# hbridge_v2.net
KiCad netlist of a schematic drawn in EAGLE
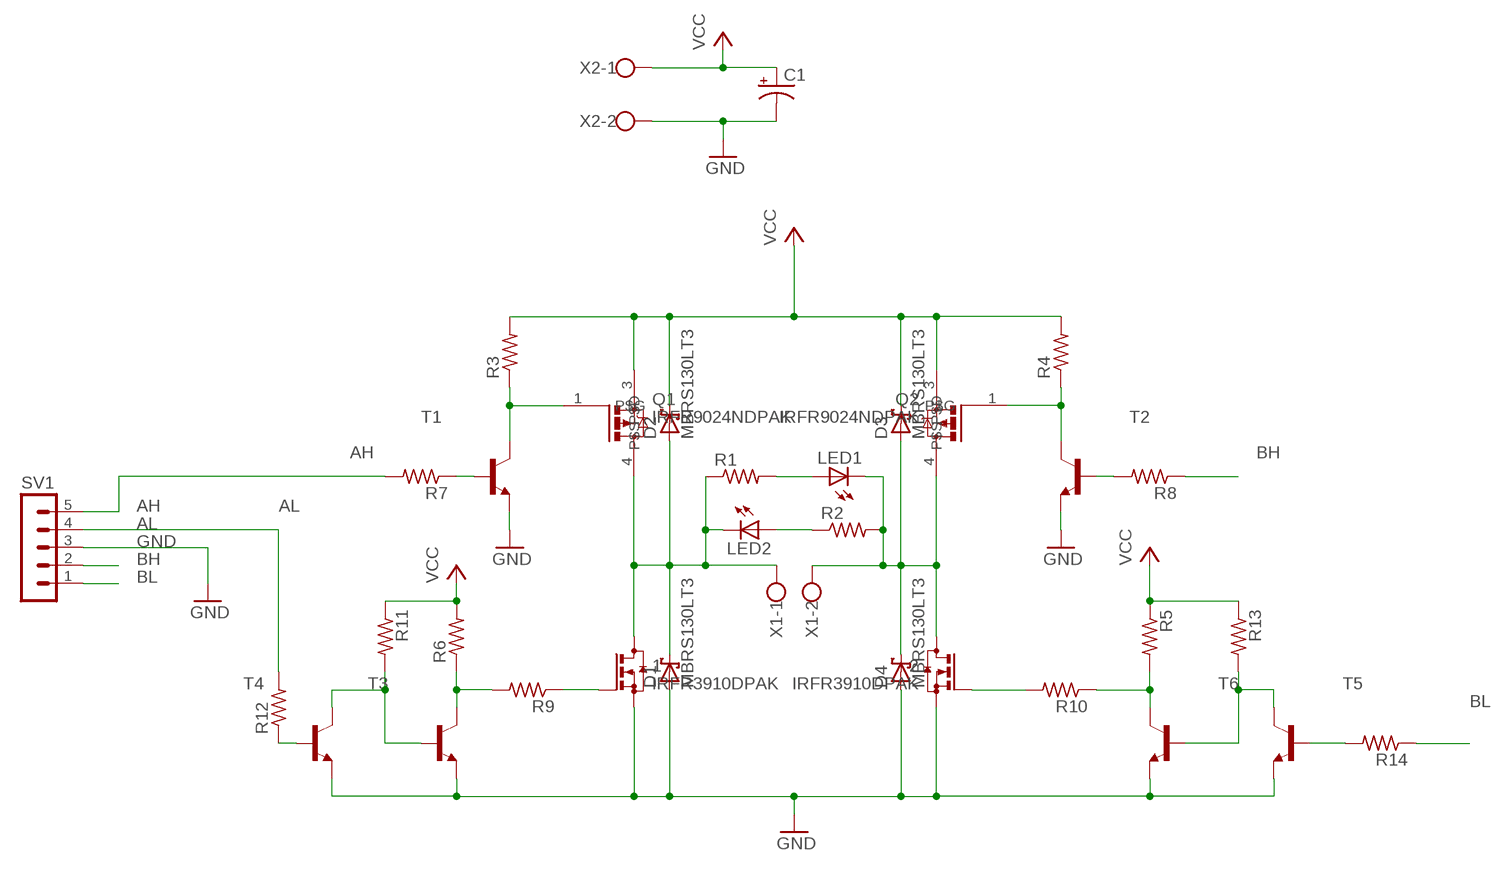
[diagram p0: schematic, sheet 1]

(export (version "E")
  (design (tool "Eeschema 10.0.6"))
  (components
    (comp (ref "1")
      (value "IRFR3910DPAK")
      (footprint "eagle-import:D-PAK_TO252AA")
      (libsource (lib "eagle-import") (part "IRFR3910DPAK"))
    )
    (comp (ref "2")
      (value "IRFR3910DPAK")
      (footprint "eagle-import:D-PAK_TO252AA")
      (libsource (lib "eagle-import") (part "IRFR3910DPAK"))
    )
    (comp (ref "C1")
      (value "CPOL-USE5-10.5")
      (footprint "eagle-import:E5-10,5")
      (libsource (lib "eagle-import") (part "CPOL-USE5-10.5"))
    )
    (comp (ref "D1")
      (value "MBRS130LT3")
      (footprint "eagle-import:SMB")
      (libsource (lib "eagle-import") (part "MBRS130LT3"))
    )
    (comp (ref "D2")
      (value "MBRS130LT3")
      (footprint "eagle-import:SMB")
      (libsource (lib "eagle-import") (part "MBRS130LT3"))
    )
    (comp (ref "D3")
      (value "MBRS130LT3")
      (footprint "eagle-import:SMB")
      (libsource (lib "eagle-import") (part "MBRS130LT3"))
    )
    (comp (ref "D4")
      (value "MBRS130LT3")
      (footprint "eagle-import:SMB")
      (libsource (lib "eagle-import") (part "MBRS130LT3"))
    )
    (comp (ref "LED1")
      (value "LEDCHIP-LED0805")
      (footprint "eagle-import:CHIP-LED0805")
      (libsource (lib "eagle-import") (part "LEDCHIP-LED0805"))
    )
    (comp (ref "LED2")
      (value "LEDCHIP-LED0805")
      (footprint "eagle-import:CHIP-LED0805")
      (libsource (lib "eagle-import") (part "LEDCHIP-LED0805"))
    )
    (comp (ref "Q1")
      (value "IRFR9024NDPAK")
      (footprint "eagle-import:D-PAK_TO252AA")
      (libsource (lib "eagle-import") (part "IRFR9024NDPAK"))
    )
    (comp (ref "Q2")
      (value "IRFR9024NDPAK")
      (footprint "eagle-import:D-PAK_TO252AA")
      (libsource (lib "eagle-import") (part "IRFR9024NDPAK"))
    )
    (comp (ref "R1")
      (value "R-US_R0805")
      (footprint "eagle-import:R0805")
      (libsource (lib "eagle-import") (part "R-US_R0805"))
    )
    (comp (ref "R2")
      (value "R-US_R0805")
      (footprint "eagle-import:R0805")
      (libsource (lib "eagle-import") (part "R-US_R0805"))
    )
    (comp (ref "R3")
      (value "R-US_R0805")
      (footprint "eagle-import:R0805")
      (libsource (lib "eagle-import") (part "R-US_R0805"))
    )
    (comp (ref "R4")
      (value "R-US_R0805")
      (footprint "eagle-import:R0805")
      (libsource (lib "eagle-import") (part "R-US_R0805"))
    )
    (comp (ref "R5")
      (value "R-US_R0805")
      (footprint "eagle-import:R0805")
      (libsource (lib "eagle-import") (part "R-US_R0805"))
    )
    (comp (ref "R6")
      (value "R-US_R0805")
      (footprint "eagle-import:R0805")
      (libsource (lib "eagle-import") (part "R-US_R0805"))
    )
    (comp (ref "R7")
      (value "R-US_R0805")
      (footprint "eagle-import:R0805")
      (libsource (lib "eagle-import") (part "R-US_R0805"))
    )
    (comp (ref "R8")
      (value "R-US_R0805")
      (footprint "eagle-import:R0805")
      (libsource (lib "eagle-import") (part "R-US_R0805"))
    )
    (comp (ref "R9")
      (value "R-US_R0805")
      (footprint "eagle-import:R0805")
      (libsource (lib "eagle-import") (part "R-US_R0805"))
    )
    (comp (ref "R10")
      (value "R-US_R0805")
      (footprint "eagle-import:R0805")
      (libsource (lib "eagle-import") (part "R-US_R0805"))
    )
    (comp (ref "R11")
      (value "R-US_R0805")
      (footprint "eagle-import:R0805")
      (libsource (lib "eagle-import") (part "R-US_R0805"))
    )
    (comp (ref "R12")
      (value "R-US_R0805")
      (footprint "eagle-import:R0805")
      (libsource (lib "eagle-import") (part "R-US_R0805"))
    )
    (comp (ref "R13")
      (value "R-US_R0805")
      (footprint "eagle-import:R0805")
      (libsource (lib "eagle-import") (part "R-US_R0805"))
    )
    (comp (ref "R14")
      (value "R-US_R0805")
      (footprint "eagle-import:R0805")
      (libsource (lib "eagle-import") (part "R-US_R0805"))
    )
    (comp (ref "SV1")
      (value "MA05-1")
      (footprint "eagle-import:MA05-1")
      (libsource (lib "eagle-import") (part "MA05-1"))
    )
    (comp (ref "T1")
      (value "MMBT2222ALT1-NPN-SOT23-BEC")
      (footprint "eagle-import:SOT23-BEC")
      (libsource (lib "eagle-import") (part "-NPN-SOT23-BECMMBT2222ALT1"))
    )
    (comp (ref "T2")
      (value "MMBT2222ALT1-NPN-SOT23-BEC")
      (footprint "eagle-import:SOT23-BEC")
      (libsource (lib "eagle-import") (part "-NPN-SOT23-BECMMBT2222ALT1"))
    )
    (comp (ref "T3")
      (value "MMBT2222ALT1-NPN-SOT23-BEC")
      (footprint "eagle-import:SOT23-BEC")
      (libsource (lib "eagle-import") (part "-NPN-SOT23-BECMMBT2222ALT1"))
    )
    (comp (ref "T4")
      (value "MMBT2222ALT1-NPN-SOT23-BEC")
      (footprint "eagle-import:SOT23-BEC")
      (libsource (lib "eagle-import") (part "-NPN-SOT23-BECMMBT2222ALT1"))
    )
    (comp (ref "T5")
      (value "MMBT2222ALT1-NPN-SOT23-BEC")
      (footprint "eagle-import:SOT23-BEC")
      (libsource (lib "eagle-import") (part "-NPN-SOT23-BECMMBT2222ALT1"))
    )
    (comp (ref "T6")
      (value "MMBT2222ALT1-NPN-SOT23-BEC")
      (footprint "eagle-import:SOT23-BEC")
      (libsource (lib "eagle-import") (part "-NPN-SOT23-BECMMBT2222ALT1"))
    )
    (comp (ref "X1")
      (value "W237-102")
      (footprint "eagle-import:W237-102")
      (fields (field (name "MPN") "237-102"))
      (libsource (lib "eagle-import") (part "W237-102"))
    )
    (comp (ref "X2")
      (value "W237-102")
      (footprint "eagle-import:W237-102")
      (fields
        (field (name "MPN") "237-102")
        (field (name "MPN_1") "237-102")
        (field (name "OC_FARNELL") "unknown")
        (field (name "OC_NEWARK") "70K9898")
      )
      (libsource (lib "eagle-import") (part "W237-102"))
    )
  )
  (nets
    (net (code "1") (name "/AH") (class "Default")
      (node (ref "R7") (pin "2") (pinfunction "2_2") (pintype "passive"))
      (node (ref "SV1") (pin "5") (pinfunction "5_5") (pintype "passive"))
    )
    (net (code "2") (name "/AL") (class "Default")
      (node (ref "R12") (pin "2") (pinfunction "2_2") (pintype "passive"))
      (node (ref "SV1") (pin "4") (pinfunction "4_4") (pintype "passive"))
    )
    (net (code "3") (name "/BH") (class "Default")
      (node (ref "R8") (pin "1") (pinfunction "1_1") (pintype "passive"))
      (node (ref "SV1") (pin "2") (pinfunction "2_2") (pintype "passive"))
    )
    (net (code "4") (name "/BL") (class "Default")
      (node (ref "R14") (pin "1") (pinfunction "1_1") (pintype "passive"))
      (node (ref "SV1") (pin "1") (pinfunction "1_1") (pintype "passive"))
    )
    (net (code "5") (name "GND") (class "Default")
      (node (ref "1") (pin "3") (pinfunction "S_3") (pintype "passive"))
      (node (ref "2") (pin "3") (pinfunction "S_3") (pintype "passive"))
      (node (ref "C1") (pin "-") (pinfunction "-_-") (pintype "passive"))
      (node (ref "D1") (pin "A") (pinfunction "A_A") (pintype "passive"))
      (node (ref "D4") (pin "A") (pinfunction "A_A") (pintype "passive"))
      (node (ref "SV1") (pin "3") (pinfunction "3_3") (pintype "passive"))
      (node (ref "T1") (pin "E") (pinfunction "E_E") (pintype "passive"))
      (node (ref "T2") (pin "E") (pinfunction "E_E") (pintype "passive"))
      (node (ref "T3") (pin "E") (pinfunction "E_E") (pintype "passive"))
      (node (ref "T4") (pin "E") (pinfunction "E_E") (pintype "passive"))
      (node (ref "T5") (pin "E") (pinfunction "E_E") (pintype "passive"))
      (node (ref "T6") (pin "E") (pinfunction "E_E") (pintype "passive"))
      (node (ref "X2") (pin "2") (pinfunction "KL_2") (pintype "passive"))
    )
    (net (code "6") (name "Net-(1-D)") (class "Default")
      (node (ref "1") (pin "4") (pinfunction "D_4") (pintype "passive"))
      (node (ref "D1") (pin "C") (pinfunction "C_C") (pintype "passive"))
      (node (ref "D2") (pin "A") (pinfunction "A_A") (pintype "passive"))
      (node (ref "LED2") (pin "C") (pinfunction "C_C") (pintype "passive"))
      (node (ref "Q1") (pin "4") (pinfunction "P$D_4") (pintype "bidirectional"))
      (node (ref "R1") (pin "1") (pinfunction "1_1") (pintype "passive"))
      (node (ref "X1") (pin "1") (pinfunction "KL_1") (pintype "passive"))
    )
    (net (code "7") (name "Net-(1-G)") (class "Default")
      (node (ref "1") (pin "1") (pinfunction "G_1") (pintype "passive"))
      (node (ref "R9") (pin "1") (pinfunction "1_1") (pintype "passive"))
    )
    (net (code "8") (name "Net-(2-D)") (class "Default")
      (node (ref "2") (pin "4") (pinfunction "D_4") (pintype "passive"))
      (node (ref "D3") (pin "A") (pinfunction "A_A") (pintype "passive"))
      (node (ref "D4") (pin "C") (pinfunction "C_C") (pintype "passive"))
      (node (ref "LED1") (pin "C") (pinfunction "C_C") (pintype "passive"))
      (node (ref "Q2") (pin "4") (pinfunction "P$D_4") (pintype "bidirectional"))
      (node (ref "R2") (pin "2") (pinfunction "2_2") (pintype "passive"))
      (node (ref "X1") (pin "2") (pinfunction "KL_2") (pintype "passive"))
    )
    (net (code "9") (name "Net-(2-G)") (class "Default")
      (node (ref "2") (pin "1") (pinfunction "G_1") (pintype "passive"))
      (node (ref "R10") (pin "2") (pinfunction "2_2") (pintype "passive"))
    )
    (net (code "10") (name "Net-(LED1-PadA)") (class "Default")
      (node (ref "LED1") (pin "A") (pinfunction "A_A") (pintype "passive"))
      (node (ref "R1") (pin "2") (pinfunction "2_2") (pintype "passive"))
    )
    (net (code "11") (name "Net-(LED2-PadA)") (class "Default")
      (node (ref "LED2") (pin "A") (pinfunction "A_A") (pintype "passive"))
      (node (ref "R2") (pin "1") (pinfunction "1_1") (pintype "passive"))
    )
    (net (code "12") (name "Net-(Q1-P$G)") (class "Default")
      (node (ref "Q1") (pin "1") (pinfunction "P$G_1") (pintype "bidirectional"))
      (node (ref "R3") (pin "1") (pinfunction "1_1") (pintype "passive"))
      (node (ref "T1") (pin "C") (pinfunction "C_C") (pintype "passive"))
    )
    (net (code "13") (name "Net-(Q2-P$G)") (class "Default")
      (node (ref "Q2") (pin "1") (pinfunction "P$G_1") (pintype "bidirectional"))
      (node (ref "R4") (pin "1") (pinfunction "1_1") (pintype "passive"))
      (node (ref "T2") (pin "C") (pinfunction "C_C") (pintype "passive"))
    )
    (net (code "14") (name "Net-(R6-Pad1)") (class "Default")
      (node (ref "R6") (pin "1") (pinfunction "1_1") (pintype "passive"))
      (node (ref "R9") (pin "2") (pinfunction "2_2") (pintype "passive"))
      (node (ref "T3") (pin "C") (pinfunction "C_C") (pintype "passive"))
    )
    (net (code "15") (name "Net-(R7-Pad1)") (class "Default")
      (node (ref "R7") (pin "1") (pinfunction "1_1") (pintype "passive"))
      (node (ref "T1") (pin "B") (pinfunction "B_B") (pintype "passive"))
    )
    (net (code "16") (name "Net-(R8-Pad2)") (class "Default")
      (node (ref "R8") (pin "2") (pinfunction "2_2") (pintype "passive"))
      (node (ref "T2") (pin "B") (pinfunction "B_B") (pintype "passive"))
    )
    (net (code "17") (name "Net-(R10-Pad1)") (class "Default")
      (node (ref "R10") (pin "1") (pinfunction "1_1") (pintype "passive"))
      (node (ref "R5") (pin "2") (pinfunction "2_2") (pintype "passive"))
      (node (ref "T6") (pin "C") (pinfunction "C_C") (pintype "passive"))
    )
    (net (code "18") (name "Net-(R11-Pad2)") (class "Default")
      (node (ref "R11") (pin "2") (pinfunction "2_2") (pintype "passive"))
      (node (ref "T3") (pin "B") (pinfunction "B_B") (pintype "passive"))
      (node (ref "T4") (pin "C") (pinfunction "C_C") (pintype "passive"))
    )
    (net (code "19") (name "Net-(R12-Pad1)") (class "Default")
      (node (ref "R12") (pin "1") (pinfunction "1_1") (pintype "passive"))
      (node (ref "T4") (pin "B") (pinfunction "B_B") (pintype "passive"))
    )
    (net (code "20") (name "Net-(R13-Pad2)") (class "Default")
      (node (ref "R13") (pin "2") (pinfunction "2_2") (pintype "passive"))
      (node (ref "T5") (pin "C") (pinfunction "C_C") (pintype "passive"))
      (node (ref "T6") (pin "B") (pinfunction "B_B") (pintype "passive"))
    )
    (net (code "21") (name "Net-(R14-Pad2)") (class "Default")
      (node (ref "R14") (pin "2") (pinfunction "2_2") (pintype "passive"))
      (node (ref "T5") (pin "B") (pinfunction "B_B") (pintype "passive"))
    )
    (net (code "22") (name "VCC") (class "Default")
      (node (ref "C1") (pin "+") (pinfunction "+_+") (pintype "passive"))
      (node (ref "D2") (pin "C") (pinfunction "C_C") (pintype "passive"))
      (node (ref "D3") (pin "C") (pinfunction "C_C") (pintype "passive"))
      (node (ref "Q1") (pin "3") (pinfunction "P$S_3") (pintype "bidirectional"))
      (node (ref "Q2") (pin "3") (pinfunction "P$S_3") (pintype "bidirectional"))
      (node (ref "R11") (pin "1") (pinfunction "1_1") (pintype "passive"))
      (node (ref "R13") (pin "1") (pinfunction "1_1") (pintype "passive"))
      (node (ref "R3") (pin "2") (pinfunction "2_2") (pintype "passive"))
      (node (ref "R4") (pin "2") (pinfunction "2_2") (pintype "passive"))
      (node (ref "R5") (pin "1") (pinfunction "1_1") (pintype "passive"))
      (node (ref "R6") (pin "2") (pinfunction "2_2") (pintype "passive"))
      (node (ref "X2") (pin "1") (pinfunction "KL_1") (pintype "passive"))
    )
  )
)
